# supply.net
KiCad netlist of a schematic drawn in Altium Designer
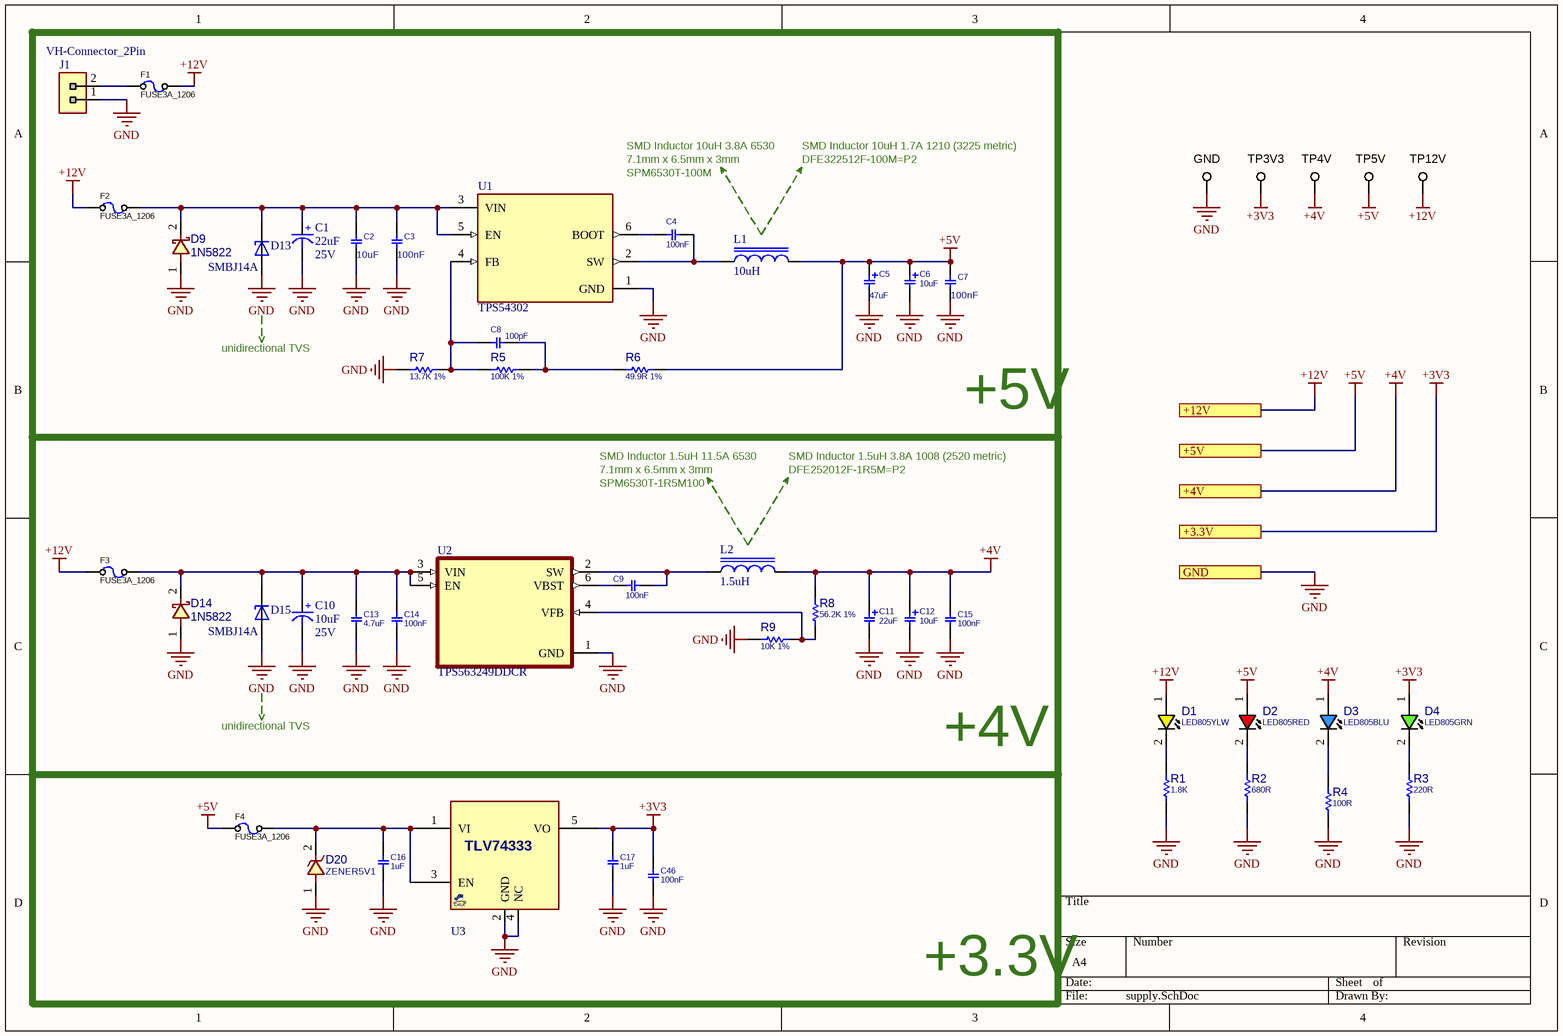
[diagram p0: supply.SchDoc]

(export (version "E")
  (design (tool "Eeschema 10.0.6"))
  (components
    (comp (ref "C1")
      (value "~")
      (footprint "Capacitor Aluminum 5.0×5.4")
      (fields (field (name "ALTIUM_UNNAMED_1") "22uF") (field (name "ALTIUM_UNNAMED_2") "25V"))
      (libsource (lib "ZetaBoard Altium Lib 14000319") (part "Capacitor Aluminum Electrolytic SMD"))
    )
    (comp (ref "C2")
      (value "10uF")
      (footprint "C1206")
      (description "CAP, MLCC")
      (fields (field (name "MANF_P#") "MANF_PART#"))
      (libsource (lib "passive_smd") (part "CAP_SMD_MLCC_1206"))
    )
    (comp (ref "C3")
      (value "100nF")
      (footprint "C1206")
      (description "CAP, MLCC")
      (fields (field (name "MANF_P#") "MANF_PART#"))
      (libsource (lib "passive_smd") (part "CAP_SMD_MLCC_1206"))
    )
    (comp (ref "C4")
      (value "100nF")
      (footprint "C0603")
      (description "CAP, MLCC, -F, -V, MATERIAL, -%, 0201")
      (fields (field (name "MANF_P#") "MANF_PART#"))
      (libsource (lib "passive_smd") (part "CAP_SMD_MLCC_0603"))
    )
    (comp (ref "C5")
      (value "47uF")
      (footprint "C_TN_3528")
      (description "CAP, SMD, TAN,")
      (libsource (lib "passive_smd") (part "CAP_SMD_TAN_3528"))
    )
    (comp (ref "C6")
      (value "10uF")
      (footprint "C_TN_3216")
      (description "CAP, SMD, TAN,")
      (libsource (lib "passive_smd") (part "CAP_SMD_TAN"))
    )
    (comp (ref "C7")
      (value "100nF")
      (footprint "C1206")
      (description "CAP, MLCC")
      (fields (field (name "MANF_P#") "MANF_PART#"))
      (libsource (lib "passive_smd") (part "CAP_SMD_MLCC_1206"))
    )
    (comp (ref "C8")
      (value "100pF")
      (footprint "C0603")
      (description "CAP, MLCC, -F, -V, MATERIAL, -%, 0201")
      (fields (field (name "MANF_P#") "MANF_PART#"))
      (libsource (lib "passive_smd") (part "CAP_SMD_MLCC_0603"))
    )
    (comp (ref "C9")
      (value "100nF")
      (footprint "C0603")
      (description "CAP, MLCC, -F, -V, MATERIAL, -%, 0201")
      (fields (field (name "MANF_P#") "MANF_PART#"))
      (libsource (lib "passive_smd") (part "CAP_SMD_MLCC_0603"))
    )
    (comp (ref "C10")
      (value "~")
      (footprint "Capacitor Aluminum 4×5.4")
      (fields (field (name "ALTIUM_UNNAMED_1") "10uF") (field (name "ALTIUM_UNNAMED_2") "25V"))
      (libsource (lib "ZetaBoard Altium Lib 14000319") (part "Capacitor Aluminum Electrolytic SMD"))
    )
    (comp (ref "C11")
      (value "22uF")
      (footprint "C_TN_3216")
      (description "CAP, SMD, TAN,")
      (libsource (lib "passive_smd") (part "CAP_SMD_TAN"))
    )
    (comp (ref "C12")
      (value "10uF")
      (footprint "C_TN_3216")
      (description "CAP, SMD, TAN,")
      (libsource (lib "passive_smd") (part "CAP_SMD_TAN"))
    )
    (comp (ref "C13")
      (value "4.7uF")
      (footprint "C1206")
      (description "CAP, MLCC, -F, -V, MATERIAL, -%, 0201")
      (fields (field (name "MANF_P#") "MANF_PART#"))
      (libsource (lib "passive_smd") (part "CAP_SMD_MLCC_1206"))
    )
    (comp (ref "C14")
      (value "100nF")
      (footprint "C1206")
      (description "CAP, MLCC, -F, -V, MATERIAL, -%, 0201")
      (fields (field (name "MANF_P#") "MANF_PART#"))
      (libsource (lib "passive_smd") (part "CAP_SMD_MLCC_1206"))
    )
    (comp (ref "C15")
      (value "100nF")
      (footprint "C1206")
      (description "CAP, MLCC, -F, -V, MATERIAL, -%, 0201")
      (fields (field (name "MANF_P#") "MANF_PART#"))
      (libsource (lib "passive_smd") (part "CAP_SMD_MLCC_1206"))
    )
    (comp (ref "C16")
      (value "1uF")
      (footprint "C1206")
      (description "CAP, MLCC, -F, -V, MATERIAL, -%, 0201")
      (fields (field (name "MANF_P#") "MANF_PART#"))
      (libsource (lib "passive_smd") (part "CAP_SMD_MLCC_1206"))
    )
    (comp (ref "C17")
      (value "1uF")
      (footprint "C1206")
      (description "CAP, MLCC, -F, -V, MATERIAL, -%, 0201")
      (fields (field (name "MANF_P#") "MANF_PART#"))
      (libsource (lib "passive_smd") (part "CAP_SMD_MLCC_1206"))
    )
    (comp (ref "C46")
      (value "100nF")
      (footprint "C1206")
      (description "CAP, MLCC, -F, -V, MATERIAL, -%, 0201")
      (fields (field (name "MANF_P#") "MANF_PART#"))
      (libsource (lib "passive_smd") (part "CAP_SMD_MLCC_1206"))
    )
    (comp (ref "D1")
      (value "LED805YLW")
      (footprint "LED0805YLW")
      (description "LED, SMD, 0805, YELLOW")
      (fields (field (name "MANF") "MANF") (field (name "MANF_P#") "MANF_PART#"))
      (libsource (lib "led(diode)") (part "LED_SMD_0805_YLW"))
    )
    (comp (ref "D2")
      (value "LED805RED")
      (footprint "LED0805RED")
      (description "LED, SMD, 0805, RED")
      (fields (field (name "MANF") "MANF") (field (name "MANF_P#") "MANF_PART#"))
      (libsource (lib "led(diode)") (part "LED_SMD_0805_RED"))
    )
    (comp (ref "D3")
      (value "LED805BLU")
      (footprint "LED0805BLU")
      (description "LED, SMD, 0805, BLUE")
      (fields (field (name "MANF") "MANF") (field (name "MANF_P#") "MANF_PART#"))
      (libsource (lib "led(diode)") (part "LED_SMD_0805_BLU"))
    )
    (comp (ref "D4")
      (value "LED805GRN")
      (footprint "LED0805GRN")
      (description "LED, SMD, 0805, GREEN")
      (libsource (lib "led(diode)") (part "LED_SMD_0805_GRN"))
    )
    (comp (ref "D9")
      (value "1N5822")
      (footprint "D_SMA")
      (description "DIODE, SCHOTTKY, 40V, 3A")
      (fields (field (name "MANF") "DIODES"))
      (libsource (lib "diode") (part "DIODE_SMD_SCHOTTKY_1N5822"))
    )
    (comp (ref "D13")
      (value "SMBJ14A")
      (footprint "SMBJ14A")
      (description "TVS Diode Uni-directional 14V SMB")
      (libsource (lib "Mehrdad") (part "SMBJ14A"))
    )
    (comp (ref "D14")
      (value "1N5822")
      (footprint "D_SMA")
      (description "DIODE, SCHOTTKY, 40V, 3A")
      (fields (field (name "MANF") "DIODES"))
      (libsource (lib "diode") (part "DIODE_SMD_SCHOTTKY_1N5822"))
    )
    (comp (ref "D15")
      (value "SMBJ14A")
      (footprint "SMBJ14A")
      (description "TVS Diode Uni-directional 14V SMB")
      (libsource (lib "Mehrdad") (part "SMBJ14A"))
    )
    (comp (ref "D20")
      (value "ZENER5V1")
      (footprint "D_SOD123W")
      (description "DIODE, ZENER, 1W, 5.1V")
      (fields (field (name "MANF") "Diodes") (field (name "MANF_P#") "BZT52HC5V1WF-7"))
      (libsource (lib "AVR_RCS") (part "DIODE_SMD_ZENER_BZT52HC5V1"))
    )
    (comp (ref "F1")
      (value "FUSE3A_1206")
      (footprint "F1206")
      (description "Fuse, 3A, 32VDC, 1206, SMD, Slow Blow")
      (fields (field (name "MANF") "Bourns") (field (name "MANF_P#") "SF-1206SP300-2"))
      (libsource (lib "protect_tvs_esd_fuse") (part "FUSE_3A_1206_SLOW"))
    )
    (comp (ref "F2")
      (value "FUSE3A_1206")
      (footprint "F1206")
      (description "Fuse, 3A, 32VDC, 1206, SMD, Slow Blow")
      (fields (field (name "MANF") "Bourns") (field (name "MANF_P#") "SF-1206SP300-2"))
      (libsource (lib "protect_tvs_esd_fuse") (part "FUSE_3A_1206_SLOW"))
    )
    (comp (ref "F3")
      (value "FUSE3A_1206")
      (footprint "F1206")
      (description "Fuse, 3A, 32VDC, 1206, SMD, Slow Blow")
      (fields (field (name "MANF") "Bourns") (field (name "MANF_P#") "SF-1206SP300-2"))
      (libsource (lib "protect_tvs_esd_fuse") (part "FUSE_3A_1206_SLOW"))
    )
    (comp (ref "F4")
      (value "FUSE3A_1206")
      (footprint "F1206")
      (description "Fuse, 3A, 32VDC, 1206, SMD, Slow Blow")
      (fields (field (name "MANF") "Bourns") (field (name "MANF_P#") "SF-1206SP300-2"))
      (libsource (lib "protect_tvs_esd_fuse") (part "FUSE_3A_1206_SLOW"))
    )
    (comp (ref "GND")
      (value "TESTPOINT_SMD")
      (footprint "TPSMD_S1")
      (description "TEST POINT")
      (fields (field (name "MANF") "MANF") (field (name "MANF_P#") "MANF_P#"))
      (libsource (lib "test-tp_jumper") (part "TESTPOINT_SMD"))
    )
    (comp (ref "J1")
      (value "VH-Connector_2Pin")
      (footprint "VH-Connector_2Pin")
      (libsource (lib "Mehrdad") (part "VH-Connector_2Pin"))
    )
    (comp (ref "L1")
      (value "10uH")
      (footprint "SMD Inductor 2")
      (description "7.1mm x 6.5mm x 3mm (6530) part number : SPM6530T-1R5M100")
      (libsource (lib "Mehrdad") (part "SMD Inductor 2"))
    )
    (comp (ref "L2")
      (value "1.5uH")
      (footprint "SMD Inductor 2")
      (description "7.1mm x 6.5mm x 3mm (6530) part number : SPM6530T-1R5M100")
      (libsource (lib "Mehrdad") (part "SMD Inductor 2"))
    )
    (comp (ref "R1")
      (value "1.8K")
      (footprint "R0805")
      (description "RESISTOR, SMD")
      (libsource (lib "passive_smd") (part "RES_SMD_0805"))
    )
    (comp (ref "R2")
      (value "680R")
      (footprint "R0805")
      (description "RESISTOR, SMD")
      (libsource (lib "passive_smd") (part "RES_SMD_0805"))
    )
    (comp (ref "R3")
      (value "220R")
      (footprint "R0805")
      (description "RESISTOR, SMD")
      (libsource (lib "passive_smd") (part "RES_SMD_0805"))
    )
    (comp (ref "R4")
      (value "100R")
      (footprint "R0805")
      (description "RESISTOR, SMD")
      (libsource (lib "passive_smd") (part "RES_SMD_0805"))
    )
    (comp (ref "R5")
      (value "100K 1%")
      (footprint "R0603")
      (description "RESISTOR, SMD")
      (libsource (lib "passive_smd") (part "RES_SMD_0603"))
    )
    (comp (ref "R6")
      (value "49.9R 1%")
      (footprint "R0603")
      (description "RESISTOR, SMD")
      (libsource (lib "passive_smd") (part "RES_SMD_0603"))
    )
    (comp (ref "R7")
      (value "13.7K 1%")
      (footprint "R0603")
      (description "RESISTOR, SMD")
      (libsource (lib "passive_smd") (part "RES_SMD_0603"))
    )
    (comp (ref "R8")
      (value "56.2K 1%")
      (footprint "R0603")
      (description "RESISTOR, SMD")
      (libsource (lib "passive_smd") (part "RES_SMD_0603"))
    )
    (comp (ref "R9")
      (value "10K 1%")
      (footprint "R0603")
      (description "RESISTOR, SMD")
      (libsource (lib "passive_smd") (part "RES_SMD_0603"))
    )
    (comp (ref "TP3V3")
      (value "TESTPOINT_SMD")
      (footprint "TPSMD_S1")
      (description "TEST POINT")
      (fields (field (name "MANF") "MANF") (field (name "MANF_P#") "MANF_P#"))
      (libsource (lib "test-tp_jumper") (part "TESTPOINT_SMD"))
    )
    (comp (ref "TP4V")
      (value "TESTPOINT_SMD")
      (footprint "TPSMD_S1")
      (description "TEST POINT")
      (fields (field (name "MANF") "MANF") (field (name "MANF_P#") "MANF_P#"))
      (libsource (lib "test-tp_jumper") (part "TESTPOINT_SMD"))
    )
    (comp (ref "TP5V")
      (value "TESTPOINT_SMD")
      (footprint "TPSMD_S1")
      (description "TEST POINT")
      (fields (field (name "MANF") "MANF") (field (name "MANF_P#") "MANF_P#"))
      (libsource (lib "test-tp_jumper") (part "TESTPOINT_SMD"))
    )
    (comp (ref "TP12V")
      (value "TESTPOINT_SMD")
      (footprint "TPSMD_S1")
      (description "TEST POINT")
      (fields (field (name "MANF") "MANF") (field (name "MANF_P#") "MANF_P#"))
      (libsource (lib "test-tp_jumper") (part "TESTPOINT_SMD"))
    )
    (comp (ref "U1")
      (value "TPS54302")
      (footprint "TPS54302")
      (description "4.5-V to 28-V Input, 3-A Output, EMI Friendly\r\nSynchronous Step-Down Converter")
      (libsource (lib "Mehrdad") (part "TPS54302"))
    )
    (comp (ref "U2")
      (value "TPS563249DDCR")
      (footprint "TPS563249DDCR")
      (description "17-V, 3-A, constant 1.4-MHz synchronous step-down voltage regulator")
      (libsource (lib "Mehrdad") (part "TPS563249DDCR"))
    )
    (comp (ref "U3")
      (value "TLV74333")
      (footprint "SOT23_5")
      (description "REG, Linear, LDO0.12V, Fixed, 300mA, VIN1.4~5.5V, VOUT1~5.5V, SOT-23-5")
      (fields (field (name "MANF") "Texas Instruments") (field (name "MANF_P#") "TLV74333PDQN"))
      (libsource (lib "pwr_reg_linear_LDO_highPSRR") (part "VREG_TLV74333_SOT23"))
    )
  )
  (nets
    (net (code "1") (name "+3V3") (class "Default")
      (node (ref "C17") (pin "1") (pinfunction "1_1") (pintype "passive"))
      (node (ref "C46") (pin "1") (pinfunction "1_1") (pintype "passive"))
      (node (ref "D4") (pin "1") (pinfunction "ANODE_1") (pintype "passive"))
      (node (ref "TP3V3") (pin "1") (pinfunction "1_1") (pintype "passive"))
      (node (ref "U3") (pin "5") (pinfunction "VO_5") (pintype "passive"))
    )
    (net (code "2") (name "+4V") (class "Default")
      (node (ref "C11") (pin "1") (pinfunction "1_1") (pintype "passive"))
      (node (ref "C12") (pin "1") (pinfunction "1_1") (pintype "passive"))
      (node (ref "C15") (pin "1") (pinfunction "1_1") (pintype "passive"))
      (node (ref "D3") (pin "1") (pinfunction "ANODE_1") (pintype "passive"))
      (node (ref "L2") (pin "2") (pinfunction "2_2") (pintype "passive"))
      (node (ref "R8") (pin "2") (pinfunction "2_2") (pintype "passive"))
      (node (ref "TP4V") (pin "1") (pinfunction "1_1") (pintype "passive"))
    )
    (net (code "3") (name "+5V") (class "Default")
      (node (ref "C5") (pin "1") (pinfunction "1_1") (pintype "passive"))
      (node (ref "C6") (pin "1") (pinfunction "1_1") (pintype "passive"))
      (node (ref "C7") (pin "2") (pinfunction "2_2") (pintype "passive"))
      (node (ref "D2") (pin "1") (pinfunction "ANODE_1") (pintype "passive"))
      (node (ref "F4") (pin "1") (pinfunction "1_1") (pintype "passive"))
      (node (ref "L1") (pin "2") (pinfunction "2_2") (pintype "passive"))
      (node (ref "R6") (pin "2") (pinfunction "2_2") (pintype "passive"))
      (node (ref "TP5V") (pin "1") (pinfunction "1_1") (pintype "passive"))
    )
    (net (code "4") (name "+12V") (class "Default")
      (node (ref "D1") (pin "1") (pinfunction "ANODE_1") (pintype "passive"))
      (node (ref "F1") (pin "2") (pinfunction "2_2") (pintype "passive"))
      (node (ref "F2") (pin "1") (pinfunction "1_1") (pintype "passive"))
      (node (ref "F3") (pin "1") (pinfunction "1_1") (pintype "passive"))
      (node (ref "TP12V") (pin "1") (pinfunction "1_1") (pintype "passive"))
    )
    (net (code "5") (name "GND") (class "Default")
      (node (ref "C1") (pin "2") (pinfunction "-_2") (pintype "passive"))
      (node (ref "C10") (pin "2") (pinfunction "-_2") (pintype "passive"))
      (node (ref "C11") (pin "2") (pinfunction "2_2") (pintype "passive"))
      (node (ref "C12") (pin "2") (pinfunction "2_2") (pintype "passive"))
      (node (ref "C13") (pin "2") (pinfunction "2_2") (pintype "passive"))
      (node (ref "C14") (pin "2") (pinfunction "2_2") (pintype "passive"))
      (node (ref "C15") (pin "2") (pinfunction "2_2") (pintype "passive"))
      (node (ref "C16") (pin "2") (pinfunction "2_2") (pintype "passive"))
      (node (ref "C17") (pin "2") (pinfunction "2_2") (pintype "passive"))
      (node (ref "C2") (pin "1") (pinfunction "1_1") (pintype "passive"))
      (node (ref "C3") (pin "1") (pinfunction "1_1") (pintype "passive"))
      (node (ref "C46") (pin "2") (pinfunction "2_2") (pintype "passive"))
      (node (ref "C5") (pin "2") (pinfunction "2_2") (pintype "passive"))
      (node (ref "C6") (pin "2") (pinfunction "2_2") (pintype "passive"))
      (node (ref "C7") (pin "1") (pinfunction "1_1") (pintype "passive"))
      (node (ref "D13") (pin "A") (pinfunction "A_A") (pintype "passive"))
      (node (ref "D14") (pin "1") (pinfunction "1_1") (pintype "passive"))
      (node (ref "D15") (pin "A") (pinfunction "A_A") (pintype "passive"))
      (node (ref "D20") (pin "1") (pinfunction "1_1") (pintype "passive"))
      (node (ref "D9") (pin "1") (pinfunction "1_1") (pintype "passive"))
      (node (ref "GND") (pin "1") (pinfunction "1_1") (pintype "passive"))
      (node (ref "J1") (pin "1") (pinfunction "1_1") (pintype "passive"))
      (node (ref "R1") (pin "2") (pinfunction "2_2") (pintype "passive"))
      (node (ref "R2") (pin "2") (pinfunction "2_2") (pintype "passive"))
      (node (ref "R3") (pin "2") (pinfunction "2_2") (pintype "passive"))
      (node (ref "R4") (pin "2") (pinfunction "2_2") (pintype "passive"))
      (node (ref "R7") (pin "1") (pinfunction "1_1") (pintype "passive"))
      (node (ref "R9") (pin "1") (pinfunction "1_1") (pintype "passive"))
      (node (ref "U1") (pin "1") (pinfunction "GND_1") (pintype "power_in"))
      (node (ref "U2") (pin "1") (pinfunction "GND_1") (pintype "power_in"))
      (node (ref "U3") (pin "2") (pinfunction "GND_2") (pintype "passive"))
      (node (ref "U3") (pin "4") (pinfunction "NC_4") (pintype "passive"))
    )
    (net (code "6") (name "Net-(C1-+)") (class "Default")
      (node (ref "C1") (pin "1") (pinfunction "+_1") (pintype "passive"))
      (node (ref "C2") (pin "2") (pinfunction "2_2") (pintype "passive"))
      (node (ref "C3") (pin "2") (pinfunction "2_2") (pintype "passive"))
      (node (ref "D13") (pin "C") (pinfunction "C_C") (pintype "passive"))
      (node (ref "D9") (pin "2") (pinfunction "2_2") (pintype "passive"))
      (node (ref "F2") (pin "2") (pinfunction "2_2") (pintype "passive"))
      (node (ref "U1") (pin "3") (pinfunction "VIN_3") (pintype "power_in"))
      (node (ref "U1") (pin "5") (pinfunction "EN_5") (pintype "input"))
    )
    (net (code "7") (name "Net-(C8-Pad2)") (class "Default")
      (node (ref "C8") (pin "2") (pinfunction "2_2") (pintype "passive"))
      (node (ref "R5") (pin "2") (pinfunction "2_2") (pintype "passive"))
      (node (ref "R6") (pin "1") (pinfunction "1_1") (pintype "passive"))
    )
    (net (code "8") (name "Net-(C10-+)") (class "Default")
      (node (ref "C10") (pin "1") (pinfunction "+_1") (pintype "passive"))
      (node (ref "C13") (pin "1") (pinfunction "1_1") (pintype "passive"))
      (node (ref "C14") (pin "1") (pinfunction "1_1") (pintype "passive"))
      (node (ref "D14") (pin "2") (pinfunction "2_2") (pintype "passive"))
      (node (ref "D15") (pin "C") (pinfunction "C_C") (pintype "passive"))
      (node (ref "F3") (pin "2") (pinfunction "2_2") (pintype "passive"))
      (node (ref "U2") (pin "3") (pinfunction "VIN_3") (pintype "input"))
      (node (ref "U2") (pin "5") (pinfunction "EN_5") (pintype "input"))
    )
    (net (code "9") (name "Net-(D1-CATHODE)") (class "Default")
      (node (ref "D1") (pin "2") (pinfunction "CATHODE_2") (pintype "passive"))
      (node (ref "R1") (pin "1") (pinfunction "1_1") (pintype "passive"))
    )
    (net (code "10") (name "Net-(D2-CATHODE)") (class "Default")
      (node (ref "D2") (pin "2") (pinfunction "CATHODE_2") (pintype "passive"))
      (node (ref "R2") (pin "1") (pinfunction "1_1") (pintype "passive"))
    )
    (net (code "11") (name "Net-(D3-CATHODE)") (class "Default")
      (node (ref "D3") (pin "2") (pinfunction "CATHODE_2") (pintype "passive"))
      (node (ref "R4") (pin "1") (pinfunction "1_1") (pintype "passive"))
    )
    (net (code "12") (name "Net-(D4-CATHODE)") (class "Default")
      (node (ref "D4") (pin "2") (pinfunction "CATHODE_2") (pintype "passive"))
      (node (ref "R3") (pin "1") (pinfunction "1_1") (pintype "passive"))
    )
    (net (code "13") (name "Net-(F1-Pad1)") (class "Default")
      (node (ref "F1") (pin "1") (pinfunction "1_1") (pintype "passive"))
      (node (ref "J1") (pin "2") (pinfunction "2_2") (pintype "passive"))
    )
    (net (code "14") (name "Net-(U1-BOOT)") (class "Default")
      (node (ref "C4") (pin "1") (pinfunction "1_1") (pintype "passive"))
      (node (ref "U1") (pin "6") (pinfunction "BOOT_6") (pintype "output"))
    )
    (net (code "15") (name "Net-(U1-FB)") (class "Default")
      (node (ref "C8") (pin "1") (pinfunction "1_1") (pintype "passive"))
      (node (ref "R5") (pin "1") (pinfunction "1_1") (pintype "passive"))
      (node (ref "R7") (pin "2") (pinfunction "2_2") (pintype "passive"))
      (node (ref "U1") (pin "4") (pinfunction "FB_4") (pintype "input"))
    )
    (net (code "16") (name "Net-(U1-SW)") (class "Default")
      (node (ref "C4") (pin "2") (pinfunction "2_2") (pintype "passive"))
      (node (ref "L1") (pin "1") (pinfunction "1_1") (pintype "passive"))
      (node (ref "U1") (pin "2") (pinfunction "SW_2") (pintype "output"))
    )
    (net (code "17") (name "Net-(U2-SW)") (class "Default")
      (node (ref "C9") (pin "2") (pinfunction "2_2") (pintype "passive"))
      (node (ref "L2") (pin "1") (pinfunction "1_1") (pintype "passive"))
      (node (ref "U2") (pin "2") (pinfunction "SW_2") (pintype "output"))
    )
    (net (code "18") (name "Net-(U2-VBST)") (class "Default")
      (node (ref "C9") (pin "1") (pinfunction "1_1") (pintype "passive"))
      (node (ref "U2") (pin "6") (pinfunction "VBST_6") (pintype "output"))
    )
    (net (code "19") (name "Net-(U2-VFB)") (class "Default")
      (node (ref "R8") (pin "1") (pinfunction "1_1") (pintype "passive"))
      (node (ref "R9") (pin "2") (pinfunction "2_2") (pintype "passive"))
      (node (ref "U2") (pin "4") (pinfunction "VFB_4") (pintype "input"))
    )
    (net (code "20") (name "Net-(U3-EN)") (class "Default")
      (node (ref "C16") (pin "1") (pinfunction "1_1") (pintype "passive"))
      (node (ref "D20") (pin "2") (pinfunction "2_2") (pintype "passive"))
      (node (ref "F4") (pin "2") (pinfunction "2_2") (pintype "passive"))
      (node (ref "U3") (pin "1") (pinfunction "VI_1") (pintype "passive"))
      (node (ref "U3") (pin "3") (pinfunction "EN_3") (pintype "passive"))
    )
  )
)
